# fdcanusb.net
KiCad netlist of a schematic drawn in EAGLE
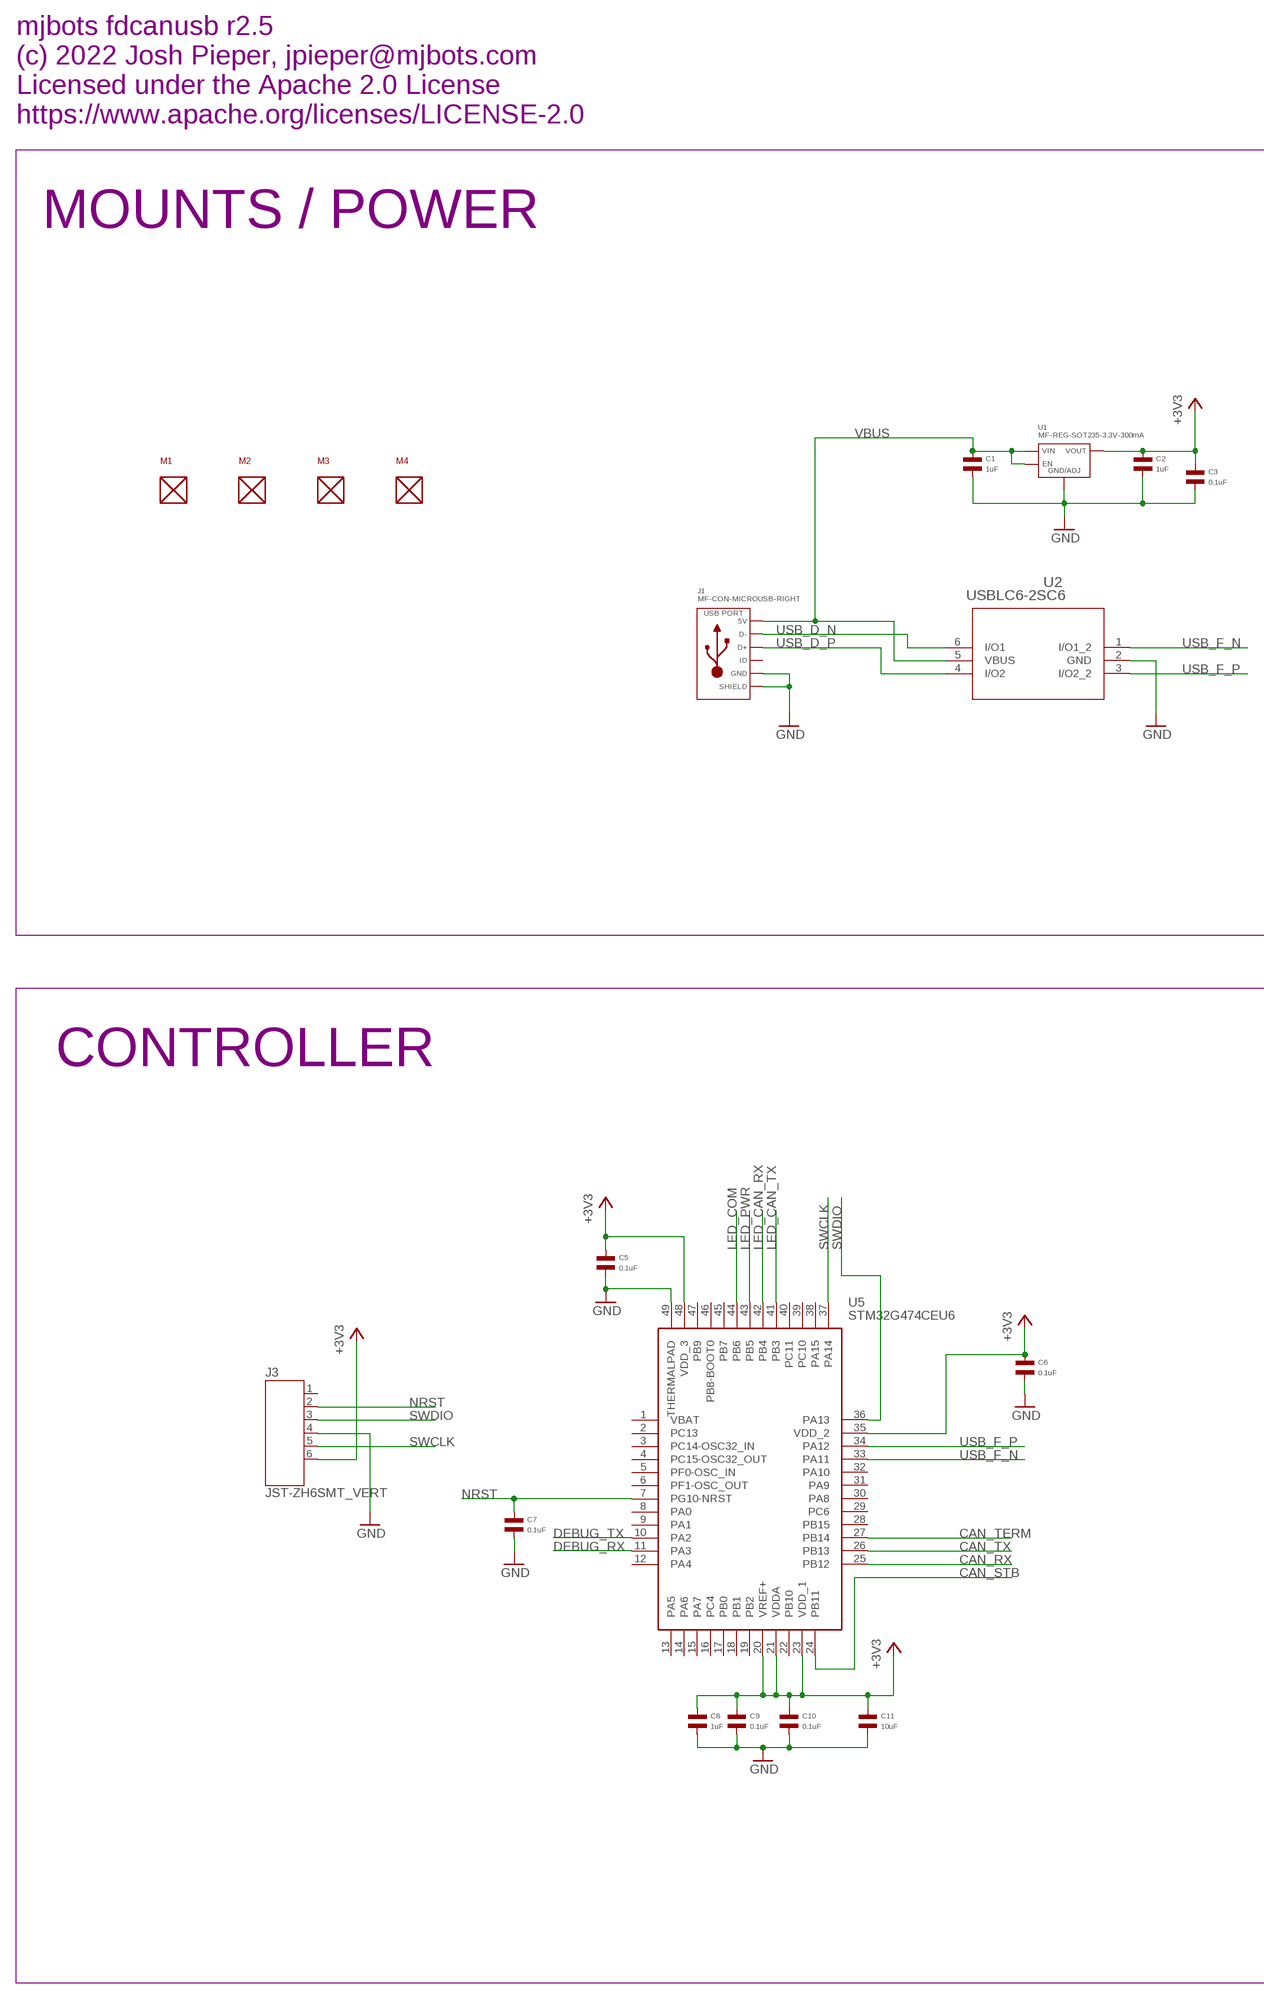
[diagram p0: schematic, sheet 1, part 1 of 2]
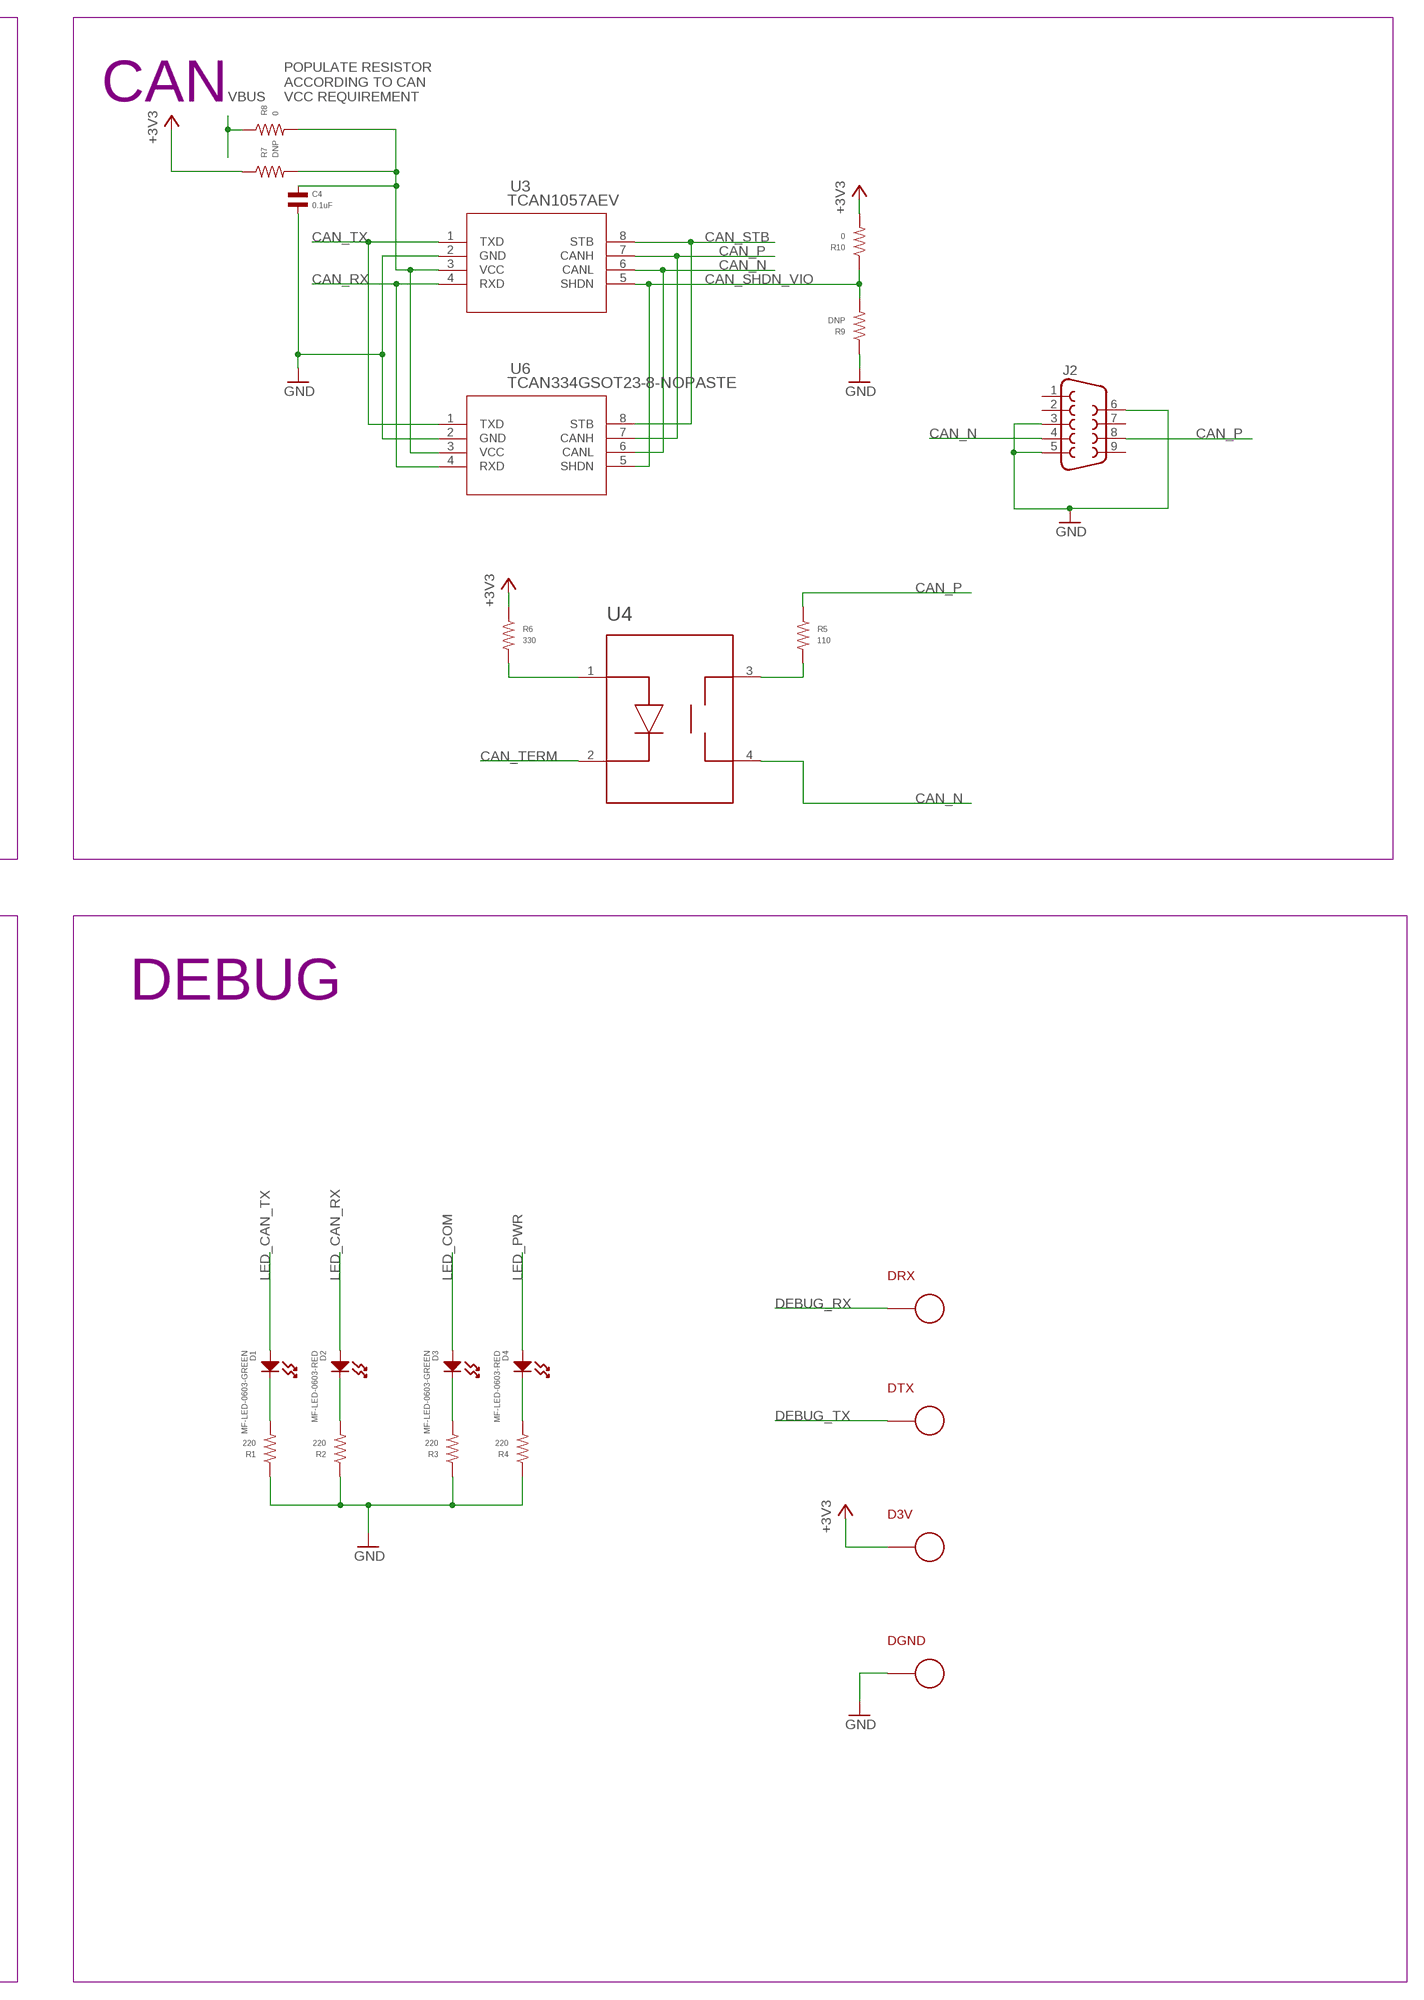
[diagram p1: schematic, sheet 1, part 2 of 2]

(export (version "E")
  (design (tool "Eeschema 10.0.6"))
  (components
    (comp (ref "C1")
      (value "1uF")
      (footprint "eagle-import:C0603")
      (fields (field (name "HOUSEPART") "YES") (field (name "MPN") "MF-CAP-0603-1uF"))
      (libsource (lib "eagle-import") (part "CAPACITOR_NP_0603"))
    )
    (comp (ref "C2")
      (value "1uF")
      (footprint "eagle-import:C0603")
      (fields (field (name "HOUSEPART") "YES") (field (name "MPN") "MF-CAP-0603-1uF"))
      (libsource (lib "eagle-import") (part "CAPACITOR_NP_0603"))
    )
    (comp (ref "C3")
      (value "0.1uF")
      (footprint "eagle-import:C0603")
      (fields (field (name "HOUSEPART") "YES") (field (name "MPN") "MF-CAP-0603-0.1uF"))
      (libsource (lib "eagle-import") (part "CAPACITOR_NP_0603"))
    )
    (comp (ref "C4")
      (value "0.1uF")
      (footprint "eagle-import:C0603")
      (fields (field (name "HOUSEPART") "YES") (field (name "MPN") "MF-CAP-0603-0.1uF"))
      (libsource (lib "eagle-import") (part "CAPACITOR_NP_0603"))
    )
    (comp (ref "C5")
      (value "0.1uF")
      (footprint "eagle-import:C0603")
      (fields (field (name "HOUSEPART") "YES") (field (name "MPN") "MF-CAP-0603-0.1uF"))
      (libsource (lib "eagle-import") (part "CAPACITOR_NP_0603"))
    )
    (comp (ref "C6")
      (value "0.1uF")
      (footprint "eagle-import:C0603")
      (fields (field (name "HOUSEPART") "YES") (field (name "MPN") "MF-CAP-0603-0.1uF"))
      (libsource (lib "eagle-import") (part "CAPACITOR_NP_0603"))
    )
    (comp (ref "C7")
      (value "0.1uF")
      (footprint "eagle-import:C0603")
      (fields (field (name "HOUSEPART") "YES") (field (name "MPN") "MF-CAP-0603-0.1uF"))
      (libsource (lib "eagle-import") (part "CAPACITOR_NP_0603"))
    )
    (comp (ref "C8")
      (value "1uF")
      (footprint "eagle-import:C0603")
      (fields (field (name "HOUSEPART") "YES") (field (name "MPN") "MF-CAP-0603-1uF"))
      (libsource (lib "eagle-import") (part "CAPACITOR_NP_0603"))
    )
    (comp (ref "C9")
      (value "0.1uF")
      (footprint "eagle-import:C0603")
      (fields (field (name "HOUSEPART") "YES") (field (name "MPN") "MF-CAP-0603-0.1uF"))
      (libsource (lib "eagle-import") (part "CAPACITOR_NP_0603"))
    )
    (comp (ref "C10")
      (value "0.1uF")
      (footprint "eagle-import:C0603")
      (fields (field (name "HOUSEPART") "YES") (field (name "MPN") "MF-CAP-0603-0.1uF"))
      (libsource (lib "eagle-import") (part "CAPACITOR_NP_0603"))
    )
    (comp (ref "C11")
      (value "10uF")
      (footprint "eagle-import:C1206")
      (fields (field (name "HOUSEPART") "YES") (field (name "MPN") "MF-CAP-1206-10uF"))
      (libsource (lib "eagle-import") (part "CAPACITOR_NP_1206"))
    )
    (comp (ref "D1")
      (value "MF-LED-0603-GREEN")
      (footprint "eagle-import:LED0603")
      (fields (field (name "HOUSEPART") "YES"))
      (libsource (lib "eagle-import") (part "LED_SINGLE-0603-GREEN"))
    )
    (comp (ref "D2")
      (value "MF-LED-0603-RED")
      (footprint "eagle-import:LED0603")
      (fields (field (name "HOUSEPART") "YES"))
      (libsource (lib "eagle-import") (part "LED_SINGLE-0603-RED"))
    )
    (comp (ref "D3")
      (value "MF-LED-0603-GREEN")
      (footprint "eagle-import:LED0603")
      (fields (field (name "HOUSEPART") "YES"))
      (libsource (lib "eagle-import") (part "LED_SINGLE-0603-GREEN"))
    )
    (comp (ref "D3V")
      (value "PAD24AWG_PAD")
      (footprint "eagle-import:24AWG_PAD")
      (libsource (lib "eagle-import") (part "PAD24AWG_PAD"))
    )
    (comp (ref "D4")
      (value "MF-LED-0603-RED")
      (footprint "eagle-import:LED0603")
      (fields (field (name "HOUSEPART") "YES"))
      (libsource (lib "eagle-import") (part "LED_SINGLE-0603-RED"))
    )
    (comp (ref "DGND")
      (value "PAD24AWG_PAD")
      (footprint "eagle-import:24AWG_PAD")
      (libsource (lib "eagle-import") (part "PAD24AWG_PAD"))
    )
    (comp (ref "DRX")
      (value "PAD24AWG_PAD")
      (footprint "eagle-import:24AWG_PAD")
      (libsource (lib "eagle-import") (part "PAD24AWG_PAD"))
    )
    (comp (ref "DTX")
      (value "PAD24AWG_PAD")
      (footprint "eagle-import:24AWG_PAD")
      (libsource (lib "eagle-import") (part "PAD24AWG_PAD"))
    )
    (comp (ref "J1")
      (value "MF-CON-MICROUSB-RIGHT")
      (footprint "eagle-import:MICROUSB-RIGHT")
      (fields (field (name "HOUSEPART") "YES"))
      (libsource (lib "eagle-import") (part "USB_MICRO_RIGHT"))
    )
    (comp (ref "J2")
      (value "F09")
      (footprint "eagle-import:DB09_PLATED")
      (libsource (lib "eagle-import") (part "F09"))
    )
    (comp (ref "J3")
      (value "JST-ZH6SMT_VERT")
      (footprint "eagle-import:JST_B6B-ZR-SM4-TF(LF)(SN)")
      (fields (field (name "MF") "JST") (field (name "MPN") "B6B-ZR-SM4-TF(LF)(SN)"))
      (libsource (lib "eagle-import") (part "JST-ZH6SMT_VERT"))
    )
    (comp (ref "M1")
      (value "MOUNT")
      (footprint "eagle-import:M2.5MOUNT")
      (libsource (lib "eagle-import") (part "MOUNT"))
    )
    (comp (ref "M2")
      (value "MOUNT")
      (footprint "eagle-import:M2.5MOUNT")
      (libsource (lib "eagle-import") (part "MOUNT"))
    )
    (comp (ref "M3")
      (value "MOUNT")
      (footprint "eagle-import:M2.5MOUNT")
      (libsource (lib "eagle-import") (part "MOUNT"))
    )
    (comp (ref "M4")
      (value "MOUNT")
      (footprint "eagle-import:M2.5MOUNT")
      (libsource (lib "eagle-import") (part "MOUNT"))
    )
    (comp (ref "R1")
      (value "220")
      (footprint "eagle-import:R0603")
      (fields (field (name "HOUSEPART") "YES") (field (name "MPN") "MF-RES-0603-220"))
      (libsource (lib "eagle-import") (part "RESISTOR_0603"))
    )
    (comp (ref "R2")
      (value "220")
      (footprint "eagle-import:R0603")
      (fields (field (name "HOUSEPART") "YES") (field (name "MPN") "MF-RES-0603-220"))
      (libsource (lib "eagle-import") (part "RESISTOR_0603"))
    )
    (comp (ref "R3")
      (value "220")
      (footprint "eagle-import:R0603")
      (fields (field (name "HOUSEPART") "YES") (field (name "MPN") "MF-RES-0603-220"))
      (libsource (lib "eagle-import") (part "RESISTOR_0603"))
    )
    (comp (ref "R4")
      (value "220")
      (footprint "eagle-import:R0603")
      (fields (field (name "HOUSEPART") "YES") (field (name "MPN") "MF-RES-0603-220"))
      (libsource (lib "eagle-import") (part "RESISTOR_0603"))
    )
    (comp (ref "R5")
      (value "110")
      (footprint "eagle-import:R0603")
      (fields (field (name "MF") "YAGEO") (field (name "MPN") "RC0603FR-07110RL"))
      (libsource (lib "eagle-import") (part "RESISTOR_0603"))
    )
    (comp (ref "R6")
      (value "330")
      (footprint "eagle-import:R0603")
      (fields (field (name "HOUSEPART") "YES") (field (name "MPN") "MF-RES-0603-330"))
      (libsource (lib "eagle-import") (part "RESISTOR_0603"))
    )
    (comp (ref "R7")
      (value "DNP")
      (footprint "eagle-import:R0603")
      (fields (field (name "HOUSEPART") "YES") (field (name "POPULATE") "0"))
      (libsource (lib "eagle-import") (part "RESISTOR_0603"))
    )
    (comp (ref "R8")
      (value "0")
      (footprint "eagle-import:R0603")
      (fields (field (name "HOUSEPART") "YES") (field (name "MPN") "MF-RES-0603-0"))
      (libsource (lib "eagle-import") (part "RESISTOR_0603"))
    )
    (comp (ref "R9")
      (value "DNP")
      (footprint "eagle-import:R0603")
      (fields (field (name "HOUSEPART") "YES") (field (name "POPULATE") "0"))
      (libsource (lib "eagle-import") (part "RESISTOR_0603"))
    )
    (comp (ref "R10")
      (value "0")
      (footprint "eagle-import:R0603")
      (fields (field (name "HOUSEPART") "YES") (field (name "MPN") "MF-RES-0603-0"))
      (libsource (lib "eagle-import") (part "RESISTOR_0603"))
    )
    (comp (ref "U1")
      (value "MF-REG-SOT235-3.3V-300mA")
      (footprint "eagle-import:SOT-23-5")
      (fields (field (name "HOUSEPART") "YES"))
      (libsource (lib "eagle-import") (part "TLV70233PDBVR"))
    )
    (comp (ref "U2")
      (value "USBLC6-2SC6")
      (footprint "eagle-import:SOT23-6L")
      (fields (field (name "MANUFACTURER_PART_NUMBER") "USBLC62SC6") (field (name "MF") "ST"))
      (libsource (lib "eagle-import") (part "USBLC6-2SC6"))
    )
    (comp (ref "U3")
      (value "TCAN1057AEV")
      (footprint "eagle-import:SOIC8")
      (fields (field (name "MF") "TI") (field (name "MPN") "TCAN1057AEVDRQ1"))
      (libsource (lib "eagle-import") (part "fdcanusb_TCAN334G"))
    )
    (comp (ref "U4")
      (value "TLP3317")
      (footprint "eagle-import:TLP3317")
      (fields
        (field (name "MF") "TOSHIBA")
        (field (name "MPN") "TLP3317(TP15,F")
        (field (name "MPN_1") "TLP3317")
      )
      (libsource (lib "eagle-import") (part "TLP3317"))
    )
    (comp (ref "U5")
      (value "STM32G474CEU6")
      (footprint "eagle-import:QFN50P700X700X60-49N")
      (fields (field (name "MOUSER_PART_NUMBER") "511-STM32G474CEU6") (field (name "MF") "ST"))
      (libsource (lib "eagle-import") (part "STM32G474CEU6"))
    )
    (comp (ref "U6")
      (value "TCAN334GSOT23-8-NOPASTE")
      (footprint "eagle-import:SOT23-8-NOPASTE")
      (fields (field (name "MF") "TI") (field (name "MPN") "TCAN334GDCNT"))
      (libsource (lib "eagle-import") (part "TCAN334GSOT23-8-NOPASTE"))
    )
  )
  (nets
    (net (code "1") (name "+3V3") (class "Default")
      (node (ref "C10") (pin "P$1") (pinfunction "P$1_P$1") (pintype "passive"))
      (node (ref "C11") (pin "P$1") (pinfunction "P$1_P$1") (pintype "passive"))
      (node (ref "C2") (pin "P$1") (pinfunction "P$1_P$1") (pintype "passive"))
      (node (ref "C3") (pin "P$1") (pinfunction "P$1_P$1") (pintype "passive"))
      (node (ref "C5") (pin "P$1") (pinfunction "P$1_P$1") (pintype "passive"))
      (node (ref "C6") (pin "P$1") (pinfunction "P$1_P$1") (pintype "passive"))
      (node (ref "C8") (pin "P$1") (pinfunction "P$1_P$1") (pintype "passive"))
      (node (ref "C9") (pin "P$1") (pinfunction "P$1_P$1") (pintype "passive"))
      (node (ref "D3V") (pin "P$1") (pinfunction "P$1_P$1") (pintype "bidirectional"))
      (node (ref "J3") (pin "6") (pinfunction "6_6") (pintype "passive"))
      (node (ref "R10") (pin "P$2") (pinfunction "P$2_P$2") (pintype "passive"))
      (node (ref "R6") (pin "P$1") (pinfunction "P$1_P$1") (pintype "passive"))
      (node (ref "R7") (pin "P$1") (pinfunction "P$1_P$1") (pintype "passive"))
      (node (ref "U1") (pin "P$5") (pinfunction "VOUT_P$5") (pintype "bidirectional"))
      (node (ref "U5") (pin "20") (pinfunction "VREF+_20") (pintype "bidirectional"))
      (node (ref "U5") (pin "21") (pinfunction "VDDA_21") (pintype "bidirectional"))
      (node (ref "U5") (pin "23") (pinfunction "VDD_1_23") (pintype "bidirectional"))
      (node (ref "U5") (pin "35") (pinfunction "VDD_2_35") (pintype "bidirectional"))
      (node (ref "U5") (pin "48") (pinfunction "VDD_3_48") (pintype "bidirectional"))
    )
    (net (code "2") (name "/CAN_N") (class "Default")
      (node (ref "J2") (pin "4") (pinfunction "4_4") (pintype "passive"))
      (node (ref "U3") (pin "6") (pinfunction "CANL_6") (pintype "bidirectional"))
      (node (ref "U4") (pin "4") (pinfunction "SW2_4") (pintype "bidirectional"))
      (node (ref "U6") (pin "6") (pinfunction "CANL_6") (pintype "bidirectional"))
    )
    (net (code "3") (name "/CAN_P") (class "Default")
      (node (ref "J2") (pin "8") (pinfunction "8_8") (pintype "passive"))
      (node (ref "R5") (pin "P$1") (pinfunction "P$1_P$1") (pintype "passive"))
      (node (ref "U3") (pin "7") (pinfunction "CANH_7") (pintype "bidirectional"))
      (node (ref "U6") (pin "7") (pinfunction "CANH_7") (pintype "bidirectional"))
    )
    (net (code "4") (name "/CAN_RX") (class "Default")
      (node (ref "U3") (pin "4") (pinfunction "RXD_4") (pintype "output"))
      (node (ref "U5") (pin "25") (pinfunction "PB12_25") (pintype "bidirectional"))
      (node (ref "U6") (pin "4") (pinfunction "RXD_4") (pintype "output"))
    )
    (net (code "5") (name "/CAN_SHDN_VIO") (class "Default")
      (node (ref "R10") (pin "P$1") (pinfunction "P$1_P$1") (pintype "passive"))
      (node (ref "R9") (pin "P$2") (pinfunction "P$2_P$2") (pintype "passive"))
      (node (ref "U3") (pin "5") (pinfunction "SHDN_5") (pintype "input"))
      (node (ref "U6") (pin "5") (pinfunction "SHDN_5") (pintype "input"))
    )
    (net (code "6") (name "/CAN_STB") (class "Default")
      (node (ref "U3") (pin "8") (pinfunction "STB_8") (pintype "input"))
      (node (ref "U5") (pin "24") (pinfunction "PB11_24") (pintype "bidirectional"))
      (node (ref "U6") (pin "8") (pinfunction "STB_8") (pintype "input"))
    )
    (net (code "7") (name "/CAN_TERM") (class "Default")
      (node (ref "U4") (pin "2") (pinfunction "CATHODE_2") (pintype "bidirectional"))
      (node (ref "U5") (pin "27") (pinfunction "PB14_27") (pintype "bidirectional"))
    )
    (net (code "8") (name "/CAN_TX") (class "Default")
      (node (ref "U3") (pin "1") (pinfunction "TXD_1") (pintype "input"))
      (node (ref "U5") (pin "26") (pinfunction "PB13_26") (pintype "bidirectional"))
      (node (ref "U6") (pin "1") (pinfunction "TXD_1") (pintype "input"))
    )
    (net (code "9") (name "/DEBUG_RX") (class "Default")
      (node (ref "DRX") (pin "P$1") (pinfunction "P$1_P$1") (pintype "bidirectional"))
      (node (ref "U5") (pin "11") (pinfunction "PA3_11") (pintype "bidirectional"))
    )
    (net (code "10") (name "/DEBUG_TX") (class "Default")
      (node (ref "DTX") (pin "P$1") (pinfunction "P$1_P$1") (pintype "bidirectional"))
      (node (ref "U5") (pin "10") (pinfunction "PA2_10") (pintype "bidirectional"))
    )
    (net (code "11") (name "/LED_CAN_RX") (class "Default")
      (node (ref "D2") (pin "ANODE") (pinfunction "ANODE_ANODE") (pintype "power_in"))
      (node (ref "U5") (pin "42") (pinfunction "PB4_42") (pintype "bidirectional"))
    )
    (net (code "12") (name "/LED_CAN_TX") (class "Default")
      (node (ref "D1") (pin "ANODE") (pinfunction "ANODE_ANODE") (pintype "power_in"))
      (node (ref "U5") (pin "41") (pinfunction "PB3_41") (pintype "bidirectional"))
    )
    (net (code "13") (name "/LED_COM") (class "Default")
      (node (ref "D3") (pin "ANODE") (pinfunction "ANODE_ANODE") (pintype "power_in"))
      (node (ref "U5") (pin "44") (pinfunction "PB6_44") (pintype "bidirectional"))
    )
    (net (code "14") (name "/LED_PWR") (class "Default")
      (node (ref "D4") (pin "ANODE") (pinfunction "ANODE_ANODE") (pintype "power_in"))
      (node (ref "U5") (pin "43") (pinfunction "PB5_43") (pintype "bidirectional"))
    )
    (net (code "15") (name "/NRST") (class "Default")
      (node (ref "C7") (pin "P$1") (pinfunction "P$1_P$1") (pintype "passive"))
      (node (ref "J3") (pin "2") (pinfunction "2_2") (pintype "passive"))
      (node (ref "U5") (pin "7") (pinfunction "PG10-NRST_7") (pintype "bidirectional"))
    )
    (net (code "16") (name "/SWCLK") (class "Default")
      (node (ref "J3") (pin "5") (pinfunction "5_5") (pintype "passive"))
      (node (ref "U5") (pin "37") (pinfunction "PA14_37") (pintype "bidirectional"))
    )
    (net (code "17") (name "/SWDIO") (class "Default")
      (node (ref "J3") (pin "3") (pinfunction "3_3") (pintype "passive"))
      (node (ref "U5") (pin "36") (pinfunction "PA13_36") (pintype "bidirectional"))
    )
    (net (code "18") (name "/USB_D_N") (class "Default")
      (node (ref "J1") (pin "2") (pinfunction "D-_2") (pintype "bidirectional"))
      (node (ref "U2") (pin "6") (pinfunction "I/O1_6") (pintype "bidirectional"))
    )
    (net (code "19") (name "/USB_D_P") (class "Default")
      (node (ref "J1") (pin "3") (pinfunction "D+_3") (pintype "bidirectional"))
      (node (ref "U2") (pin "4") (pinfunction "I/O2_4") (pintype "bidirectional"))
    )
    (net (code "20") (name "/USB_F_N") (class "Default")
      (node (ref "U2") (pin "1") (pinfunction "I/O1_2_1") (pintype "bidirectional"))
      (node (ref "U5") (pin "33") (pinfunction "PA11_33") (pintype "bidirectional"))
    )
    (net (code "21") (name "/USB_F_P") (class "Default")
      (node (ref "U2") (pin "3") (pinfunction "I/O2_2_3") (pintype "bidirectional"))
      (node (ref "U5") (pin "34") (pinfunction "PA12_34") (pintype "bidirectional"))
    )
    (net (code "22") (name "/VBUS") (class "Default")
      (node (ref "C1") (pin "P$1") (pinfunction "P$1_P$1") (pintype "passive"))
      (node (ref "J1") (pin "1") (pinfunction "5V_1") (pintype "power_in"))
      (node (ref "R8") (pin "P$1") (pinfunction "P$1_P$1") (pintype "passive"))
      (node (ref "U1") (pin "P$1") (pinfunction "VIN_P$1") (pintype "bidirectional"))
      (node (ref "U1") (pin "P$3") (pinfunction "EN_P$3") (pintype "bidirectional"))
      (node (ref "U2") (pin "5") (pinfunction "VBUS_5") (pintype "power_in"))
    )
    (net (code "23") (name "GND") (class "Default")
      (node (ref "C1") (pin "P$2") (pinfunction "P$2_P$2") (pintype "passive"))
      (node (ref "C10") (pin "P$2") (pinfunction "P$2_P$2") (pintype "passive"))
      (node (ref "C11") (pin "P$2") (pinfunction "P$2_P$2") (pintype "passive"))
      (node (ref "C2") (pin "P$2") (pinfunction "P$2_P$2") (pintype "passive"))
      (node (ref "C3") (pin "P$2") (pinfunction "P$2_P$2") (pintype "passive"))
      (node (ref "C4") (pin "P$2") (pinfunction "P$2_P$2") (pintype "passive"))
      (node (ref "C5") (pin "P$2") (pinfunction "P$2_P$2") (pintype "passive"))
      (node (ref "C6") (pin "P$2") (pinfunction "P$2_P$2") (pintype "passive"))
      (node (ref "C7") (pin "P$2") (pinfunction "P$2_P$2") (pintype "passive"))
      (node (ref "C8") (pin "P$2") (pinfunction "P$2_P$2") (pintype "passive"))
      (node (ref "C9") (pin "P$2") (pinfunction "P$2_P$2") (pintype "passive"))
      (node (ref "DGND") (pin "P$1") (pinfunction "P$1_P$1") (pintype "bidirectional"))
      (node (ref "J1") (pin "5") (pinfunction "GND_5") (pintype "power_in"))
      (node (ref "J1") (pin "S1") (pinfunction "SLD_S1") (pintype "power_in"))
      (node (ref "J1") (pin "S2") (pinfunction "SLD_S2") (pintype "power_in"))
      (node (ref "J1") (pin "S3") (pinfunction "SLD_S3") (pintype "power_in"))
      (node (ref "J1") (pin "S4") (pinfunction "SLD_S4") (pintype "power_in"))
      (node (ref "J1") (pin "S5") (pinfunction "SLD_S5") (pintype "power_in"))
      (node (ref "J1") (pin "S6") (pinfunction "SLD_S6") (pintype "power_in"))
      (node (ref "J2") (pin "3") (pinfunction "3_3") (pintype "passive"))
      (node (ref "J2") (pin "5") (pinfunction "5_5") (pintype "passive"))
      (node (ref "J2") (pin "6") (pinfunction "6_6") (pintype "passive"))
      (node (ref "J3") (pin "4") (pinfunction "4_4") (pintype "passive"))
      (node (ref "R1") (pin "P$1") (pinfunction "P$1_P$1") (pintype "passive"))
      (node (ref "R2") (pin "P$1") (pinfunction "P$1_P$1") (pintype "passive"))
      (node (ref "R3") (pin "P$1") (pinfunction "P$1_P$1") (pintype "passive"))
      (node (ref "R4") (pin "P$1") (pinfunction "P$1_P$1") (pintype "passive"))
      (node (ref "R9") (pin "P$1") (pinfunction "P$1_P$1") (pintype "passive"))
      (node (ref "U1") (pin "P$2") (pinfunction "GND/ADJ_P$2") (pintype "bidirectional"))
      (node (ref "U2") (pin "2") (pinfunction "GND_2") (pintype "power_in"))
      (node (ref "U3") (pin "2") (pinfunction "GND_2") (pintype "power_in"))
      (node (ref "U5") (pin "49") (pinfunction "THERMALPAD_49") (pintype "bidirectional"))
      (node (ref "U6") (pin "2") (pinfunction "GND_2") (pintype "power_in"))
    )
    (net (code "24") (name "Net-(D1-PadCATHODE)") (class "Default")
      (node (ref "D1") (pin "CATHODE") (pinfunction "CATHODE_CATHODE") (pintype "power_in"))
      (node (ref "R1") (pin "P$2") (pinfunction "P$2_P$2") (pintype "passive"))
    )
    (net (code "25") (name "Net-(D2-PadCATHODE)") (class "Default")
      (node (ref "D2") (pin "CATHODE") (pinfunction "CATHODE_CATHODE") (pintype "power_in"))
      (node (ref "R2") (pin "P$2") (pinfunction "P$2_P$2") (pintype "passive"))
    )
    (net (code "26") (name "Net-(D3-PadCATHODE)") (class "Default")
      (node (ref "D3") (pin "CATHODE") (pinfunction "CATHODE_CATHODE") (pintype "power_in"))
      (node (ref "R3") (pin "P$2") (pinfunction "P$2_P$2") (pintype "passive"))
    )
    (net (code "27") (name "Net-(D4-PadCATHODE)") (class "Default")
      (node (ref "D4") (pin "CATHODE") (pinfunction "CATHODE_CATHODE") (pintype "power_in"))
      (node (ref "R4") (pin "P$2") (pinfunction "P$2_P$2") (pintype "passive"))
    )
    (net (code "28") (name "Net-(U3-VCC)") (class "Default")
      (node (ref "C4") (pin "P$1") (pinfunction "P$1_P$1") (pintype "passive"))
      (node (ref "R7") (pin "P$2") (pinfunction "P$2_P$2") (pintype "passive"))
      (node (ref "R8") (pin "P$2") (pinfunction "P$2_P$2") (pintype "passive"))
      (node (ref "U3") (pin "3") (pinfunction "VCC_3") (pintype "power_in"))
      (node (ref "U6") (pin "3") (pinfunction "VCC_3") (pintype "power_in"))
    )
    (net (code "29") (name "Net-(U4-ANODE)") (class "Default")
      (node (ref "R6") (pin "P$2") (pinfunction "P$2_P$2") (pintype "passive"))
      (node (ref "U4") (pin "1") (pinfunction "ANODE_1") (pintype "bidirectional"))
    )
    (net (code "30") (name "Net-(U4-SW1)") (class "Default")
      (node (ref "R5") (pin "P$2") (pinfunction "P$2_P$2") (pintype "passive"))
      (node (ref "U4") (pin "3") (pinfunction "SW1_3") (pintype "bidirectional"))
    )
    (net (code "31") (name "unconnected-(J1-ID-Pad4)") (class "Default")
      (node (ref "J1") (pin "4") (pinfunction "ID_4") (pintype "bidirectional"))
    )
    (net (code "32") (name "unconnected-(J2-Pad1)") (class "Default")
      (node (ref "J2") (pin "1") (pinfunction "1_1") (pintype "passive"))
    )
    (net (code "33") (name "unconnected-(J2-Pad2)") (class "Default")
      (node (ref "J2") (pin "2") (pinfunction "2_2") (pintype "passive"))
    )
    (net (code "34") (name "unconnected-(J2-Pad7)") (class "Default")
      (node (ref "J2") (pin "7") (pinfunction "7_7") (pintype "passive"))
    )
    (net (code "35") (name "unconnected-(J2-Pad9)") (class "Default")
      (node (ref "J2") (pin "9") (pinfunction "9_9") (pintype "passive"))
    )
    (net (code "36") (name "unconnected-(J3-Pad1)") (class "Default")
      (node (ref "J3") (pin "1") (pinfunction "1_1") (pintype "passive"))
    )
    (net (code "37") (name "unconnected-(U5-PA0-Pad8)") (class "Default")
      (node (ref "U5") (pin "8") (pinfunction "PA0_8") (pintype "bidirectional"))
    )
    (net (code "38") (name "unconnected-(U5-PA1-Pad9)") (class "Default")
      (node (ref "U5") (pin "9") (pinfunction "PA1_9") (pintype "bidirectional"))
    )
    (net (code "39") (name "unconnected-(U5-PA4-Pad12)") (class "Default")
      (node (ref "U5") (pin "12") (pinfunction "PA4_12") (pintype "bidirectional"))
    )
    (net (code "40") (name "unconnected-(U5-PA5-Pad13)") (class "Default")
      (node (ref "U5") (pin "13") (pinfunction "PA5_13") (pintype "bidirectional"))
    )
    (net (code "41") (name "unconnected-(U5-PA6-Pad14)") (class "Default")
      (node (ref "U5") (pin "14") (pinfunction "PA6_14") (pintype "bidirectional"))
    )
    (net (code "42") (name "unconnected-(U5-PA7-Pad15)") (class "Default")
      (node (ref "U5") (pin "15") (pinfunction "PA7_15") (pintype "bidirectional"))
    )
    (net (code "43") (name "unconnected-(U5-PA8-Pad30)") (class "Default")
      (node (ref "U5") (pin "30") (pinfunction "PA8_30") (pintype "bidirectional"))
    )
    (net (code "44") (name "unconnected-(U5-PA9-Pad31)") (class "Default")
      (node (ref "U5") (pin "31") (pinfunction "PA9_31") (pintype "bidirectional"))
    )
    (net (code "45") (name "unconnected-(U5-PA10-Pad32)") (class "Default")
      (node (ref "U5") (pin "32") (pinfunction "PA10_32") (pintype "bidirectional"))
    )
    (net (code "46") (name "unconnected-(U5-PA15-Pad38)") (class "Default")
      (node (ref "U5") (pin "38") (pinfunction "PA15_38") (pintype "bidirectional"))
    )
    (net (code "47") (name "unconnected-(U5-PB0-Pad17)") (class "Default")
      (node (ref "U5") (pin "17") (pinfunction "PB0_17") (pintype "bidirectional"))
    )
    (net (code "48") (name "unconnected-(U5-PB1-Pad18)") (class "Default")
      (node (ref "U5") (pin "18") (pinfunction "PB1_18") (pintype "bidirectional"))
    )
    (net (code "49") (name "unconnected-(U5-PB2-Pad19)") (class "Default")
      (node (ref "U5") (pin "19") (pinfunction "PB2_19") (pintype "bidirectional"))
    )
    (net (code "50") (name "unconnected-(U5-PB7-Pad45)") (class "Default")
      (node (ref "U5") (pin "45") (pinfunction "PB7_45") (pintype "bidirectional"))
    )
    (net (code "51") (name "unconnected-(U5-PB8-BOOT0-Pad46)") (class "Default")
      (node (ref "U5") (pin "46") (pinfunction "PB8-BOOT0_46") (pintype "bidirectional"))
    )
    (net (code "52") (name "unconnected-(U5-PB9-Pad47)") (class "Default")
      (node (ref "U5") (pin "47") (pinfunction "PB9_47") (pintype "bidirectional"))
    )
    (net (code "53") (name "unconnected-(U5-PB10-Pad22)") (class "Default")
      (node (ref "U5") (pin "22") (pinfunction "PB10_22") (pintype "bidirectional"))
    )
    (net (code "54") (name "unconnected-(U5-PB15-Pad28)") (class "Default")
      (node (ref "U5") (pin "28") (pinfunction "PB15_28") (pintype "bidirectional"))
    )
    (net (code "55") (name "unconnected-(U5-PC4-Pad16)") (class "Default")
      (node (ref "U5") (pin "16") (pinfunction "PC4_16") (pintype "bidirectional"))
    )
    (net (code "56") (name "unconnected-(U5-PC6-Pad29)") (class "Default")
      (node (ref "U5") (pin "29") (pinfunction "PC6_29") (pintype "bidirectional"))
    )
    (net (code "57") (name "unconnected-(U5-PC10-Pad39)") (class "Default")
      (node (ref "U5") (pin "39") (pinfunction "PC10_39") (pintype "bidirectional"))
    )
    (net (code "58") (name "unconnected-(U5-PC11-Pad40)") (class "Default")
      (node (ref "U5") (pin "40") (pinfunction "PC11_40") (pintype "bidirectional"))
    )
    (net (code "59") (name "unconnected-(U5-PC13-Pad2)") (class "Default")
      (node (ref "U5") (pin "2") (pinfunction "PC13_2") (pintype "bidirectional"))
    )
    (net (code "60") (name "unconnected-(U5-PC14-OSC32_IN-Pad3)") (class "Default")
      (node (ref "U5") (pin "3") (pinfunction "PC14-OSC32_IN_3") (pintype "bidirectional"))
    )
    (net (code "61") (name "unconnected-(U5-PC15-OSC32_OUT-Pad4)") (class "Default")
      (node (ref "U5") (pin "4") (pinfunction "PC15-OSC32_OUT_4") (pintype "bidirectional"))
    )
    (net (code "62") (name "unconnected-(U5-PF0-OSC_IN-Pad5)") (class "Default")
      (node (ref "U5") (pin "5") (pinfunction "PF0-OSC_IN_5") (pintype "bidirectional"))
    )
    (net (code "63") (name "unconnected-(U5-PF1-OSC_OUT-Pad6)") (class "Default")
      (node (ref "U5") (pin "6") (pinfunction "PF1-OSC_OUT_6") (pintype "bidirectional"))
    )
    (net (code "64") (name "unconnected-(U5-VBAT-Pad1)") (class "Default")
      (node (ref "U5") (pin "1") (pinfunction "VBAT_1") (pintype "bidirectional"))
    )
  )
)
